# HM_Nightfall-mini_v1.net
KiCad netlist of a schematic drawn in EAGLE
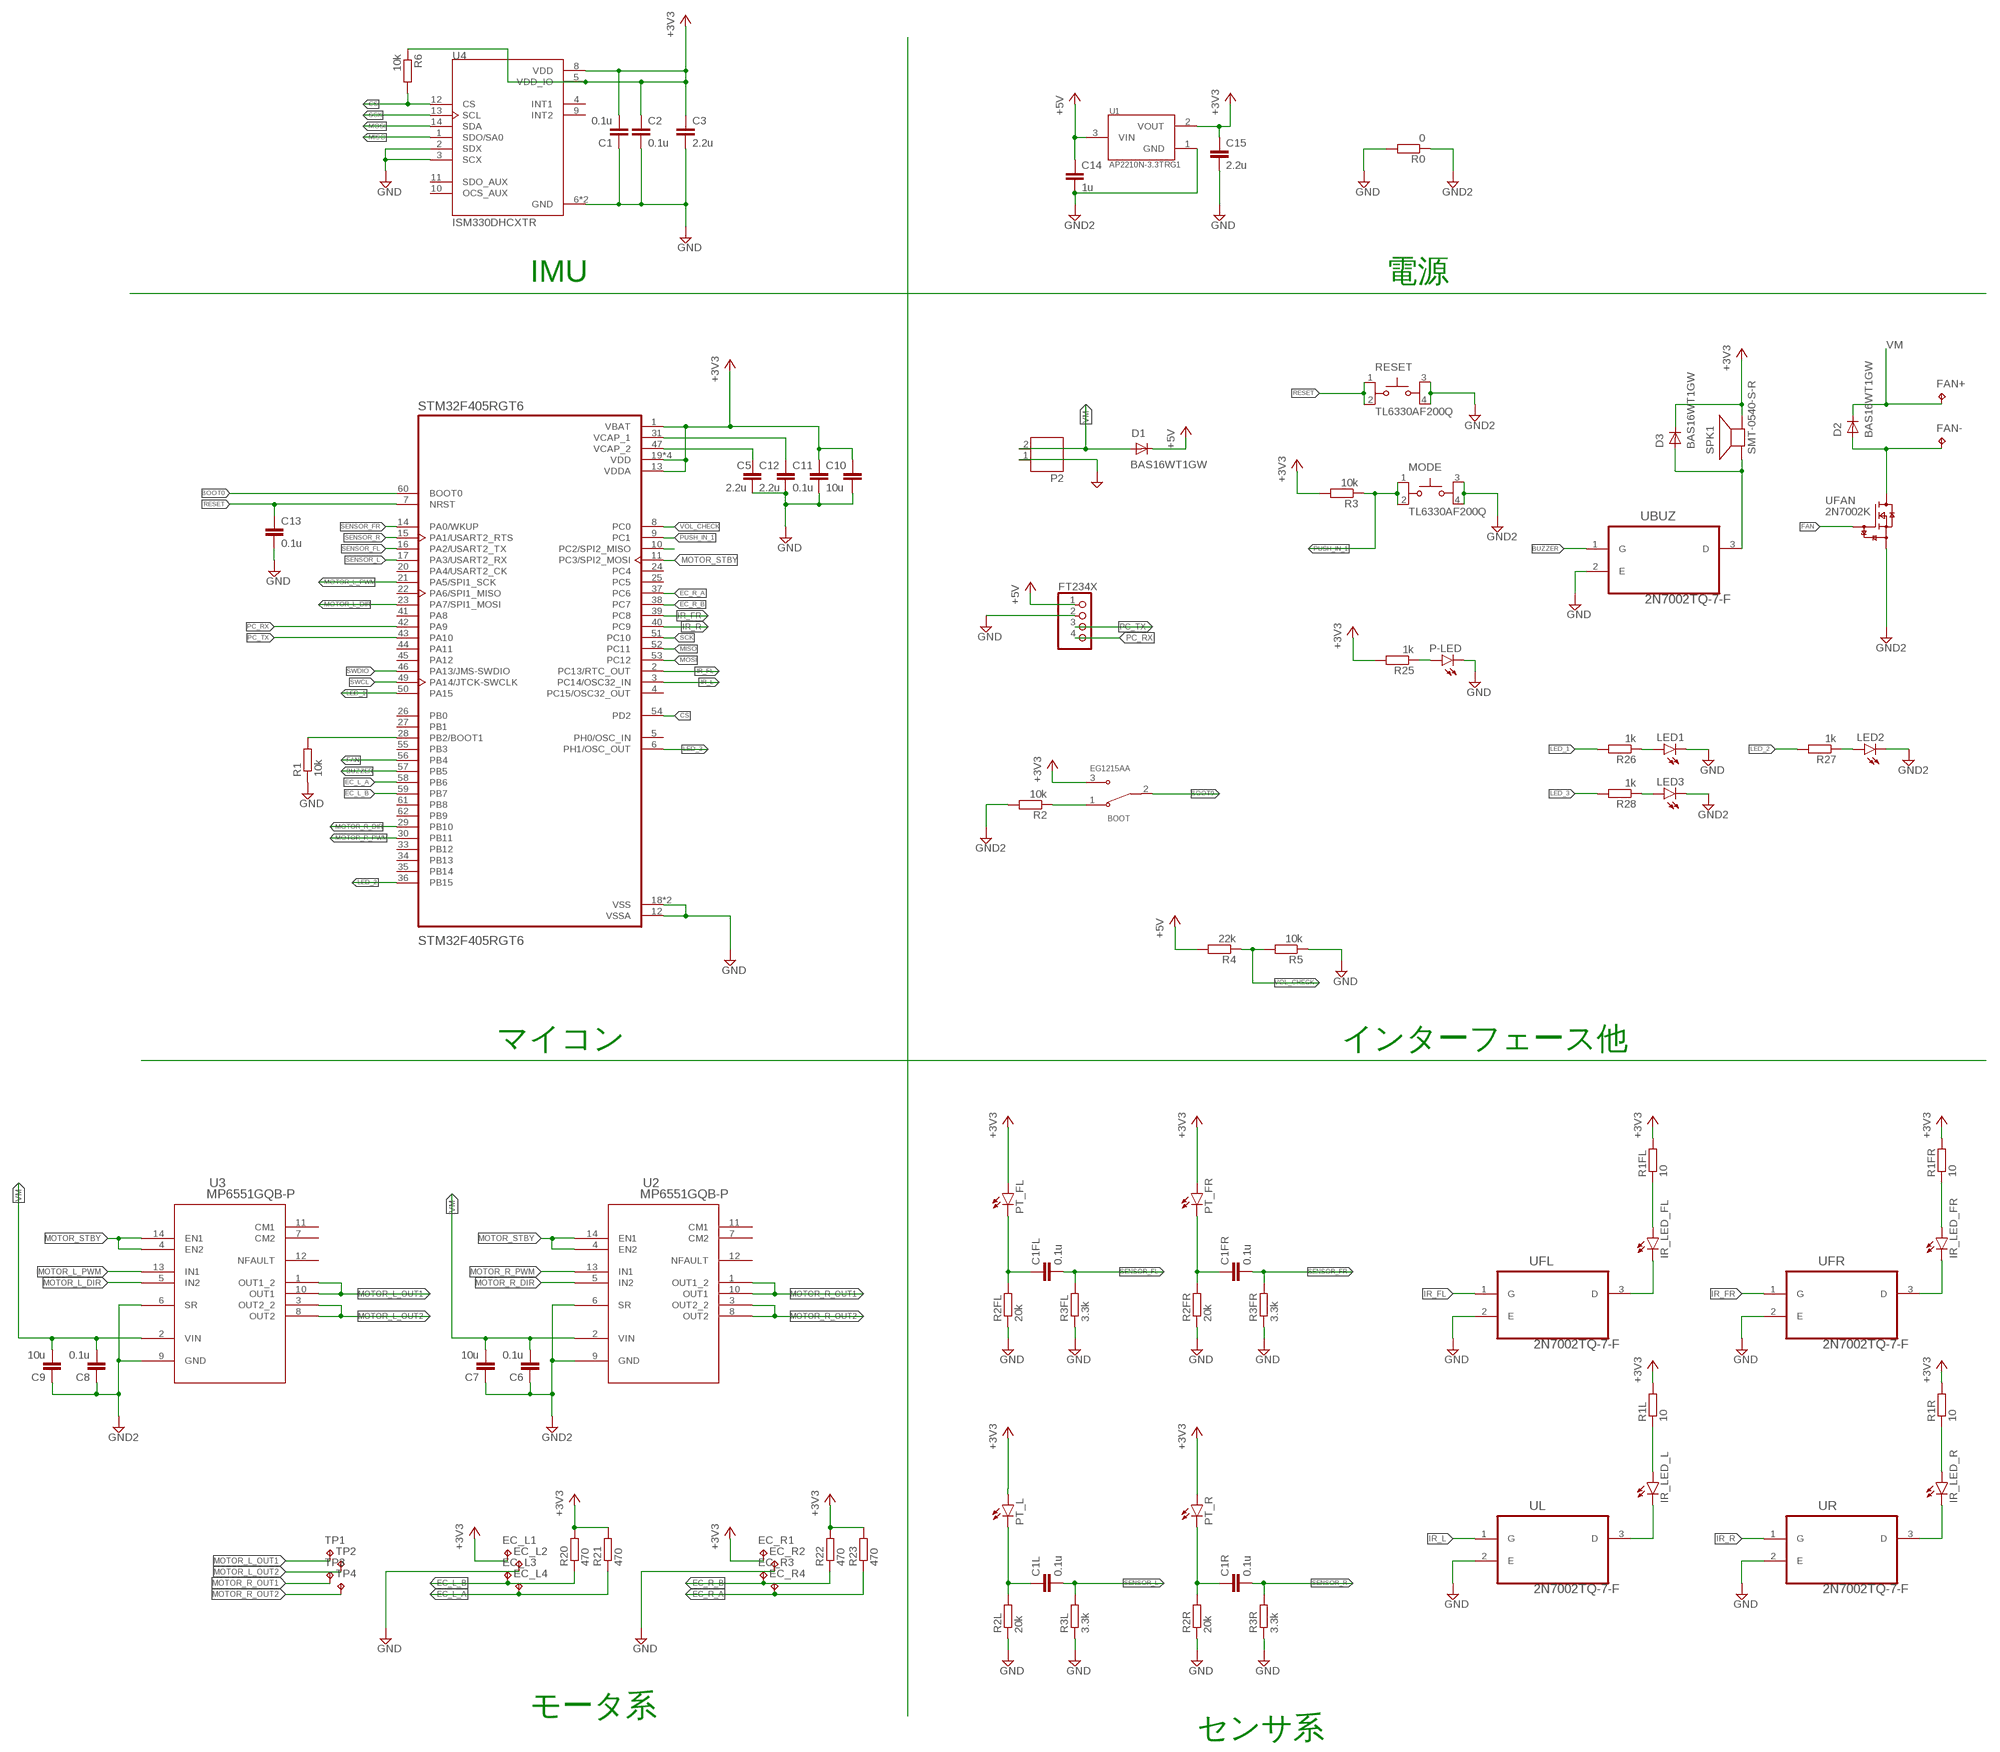
[diagram p0: schematic, sheet 1]

(export (version "E")
  (design (tool "Eeschema 10.0.6"))
  (components
    (comp (ref "BOOT")
      (value "EG1215AA")
      (footprint "eagle-import:SW_EG1215AA")
      (fields (field (name "MF") "E-Switch"))
      (libsource (lib "eagle-import") (part "EG1215AA"))
    )
    (comp (ref "C1")
      (value "0.1u")
      (footprint "eagle-import:C0402")
      (libsource (lib "eagle-import") (part "C-EUC0402"))
    )
    (comp (ref "C1FL")
      (value "0.1u")
      (footprint "eagle-import:C0402")
      (libsource (lib "eagle-import") (part "C-EUC0402"))
    )
    (comp (ref "C1FR")
      (value "0.1u")
      (footprint "eagle-import:C0402")
      (libsource (lib "eagle-import") (part "C-EUC0402"))
    )
    (comp (ref "C1L")
      (value "0.1u")
      (footprint "eagle-import:C0402")
      (libsource (lib "eagle-import") (part "C-EUC0402"))
    )
    (comp (ref "C1R")
      (value "0.1u")
      (footprint "eagle-import:C0402")
      (libsource (lib "eagle-import") (part "C-EUC0402"))
    )
    (comp (ref "C2")
      (value "0.1u")
      (footprint "eagle-import:C0402")
      (libsource (lib "eagle-import") (part "C-EUC0402"))
    )
    (comp (ref "C3")
      (value "2.2u")
      (footprint "eagle-import:C0402")
      (libsource (lib "eagle-import") (part "C-EUC0402"))
    )
    (comp (ref "C5")
      (value "2.2u")
      (footprint "eagle-import:C0402")
      (libsource (lib "eagle-import") (part "C-EUC0402"))
    )
    (comp (ref "C6")
      (value "0.1u")
      (footprint "eagle-import:C0402")
      (libsource (lib "eagle-import") (part "C-EUC0402"))
    )
    (comp (ref "C7")
      (value "10u")
      (footprint "eagle-import:C0402")
      (libsource (lib "eagle-import") (part "C-EUC0402"))
    )
    (comp (ref "C8")
      (value "0.1u")
      (footprint "eagle-import:C0402")
      (libsource (lib "eagle-import") (part "C-EUC0402"))
    )
    (comp (ref "C9")
      (value "10u")
      (footprint "eagle-import:C0402")
      (libsource (lib "eagle-import") (part "C-EUC0402"))
    )
    (comp (ref "C10")
      (value "10u")
      (footprint "eagle-import:C0402")
      (libsource (lib "eagle-import") (part "C-EUC0402"))
    )
    (comp (ref "C11")
      (value "0.1u")
      (footprint "eagle-import:C0402")
      (libsource (lib "eagle-import") (part "C-EUC0402"))
    )
    (comp (ref "C12")
      (value "2.2u")
      (footprint "eagle-import:C0402")
      (libsource (lib "eagle-import") (part "C-EUC0402"))
    )
    (comp (ref "C13")
      (value "0.1u")
      (footprint "eagle-import:C0402")
      (libsource (lib "eagle-import") (part "C-EUC0402"))
    )
    (comp (ref "C14")
      (value "1u")
      (footprint "eagle-import:C0402")
      (libsource (lib "eagle-import") (part "C-EUC0402"))
    )
    (comp (ref "C15")
      (value "2.2u")
      (footprint "eagle-import:C0402")
      (libsource (lib "eagle-import") (part "C-EUC0402"))
    )
    (comp (ref "D1")
      (value "BAS16WT1GW")
      (footprint "eagle-import:SOT323")
      (fields (field (name "MF") "ON Semiconductor") (field (name "MP") "BAS16WT1G"))
      (libsource (lib "eagle-import") (part "BAS16WT1GW"))
    )
    (comp (ref "D2")
      (value "BAS16WT1GW")
      (footprint "eagle-import:SOT323")
      (fields (field (name "MF") "ON Semiconductor") (field (name "MP") "BAS16WT1G"))
      (libsource (lib "eagle-import") (part "BAS16WT1GW"))
    )
    (comp (ref "D3")
      (value "BAS16WT1GW")
      (footprint "eagle-import:SOT323")
      (fields (field (name "MF") "ON Semiconductor") (field (name "MP") "BAS16WT1G"))
      (libsource (lib "eagle-import") (part "BAS16WT1GW"))
    )
    (comp (ref "EC_L1")
      (value "TPB1,27")
      (footprint "eagle-import:B1,27")
      (libsource (lib "eagle-import") (part "TPB1,27"))
    )
    (comp (ref "EC_L2")
      (value "TPB1,27")
      (footprint "eagle-import:B1,27")
      (libsource (lib "eagle-import") (part "TPB1,27"))
    )
    (comp (ref "EC_L3")
      (value "TPB1,27")
      (footprint "eagle-import:B1,27")
      (libsource (lib "eagle-import") (part "TPB1,27"))
    )
    (comp (ref "EC_L4")
      (value "TPB1,27")
      (footprint "eagle-import:B1,27")
      (libsource (lib "eagle-import") (part "TPB1,27"))
    )
    (comp (ref "EC_R1")
      (value "TPB1,27")
      (footprint "eagle-import:B1,27")
      (libsource (lib "eagle-import") (part "TPB1,27"))
    )
    (comp (ref "EC_R2")
      (value "TPB1,27")
      (footprint "eagle-import:B1,27")
      (libsource (lib "eagle-import") (part "TPB1,27"))
    )
    (comp (ref "EC_R3")
      (value "TPB1,27")
      (footprint "eagle-import:B1,27")
      (libsource (lib "eagle-import") (part "TPB1,27"))
    )
    (comp (ref "EC_R4")
      (value "TPB1,27")
      (footprint "eagle-import:B1,27")
      (libsource (lib "eagle-import") (part "TPB1,27"))
    )
    (comp (ref "FAN+")
      (value "TPB1,27")
      (footprint "eagle-import:B1,27")
      (libsource (lib "eagle-import") (part "TPB1,27"))
    )
    (comp (ref "FAN-")
      (value "TPB1,27")
      (footprint "eagle-import:B1,27")
      (libsource (lib "eagle-import") (part "TPB1,27"))
    )
    (comp (ref "FT234X")
      (value "PINHD-1X4")
      (footprint "eagle-import:1X04")
      (libsource (lib "eagle-import") (part "PINHD-1X4"))
    )
    (comp (ref "IR_LED_FL")
      (value "LED3MM")
      (footprint "eagle-import:LED3MM")
      (libsource (lib "eagle-import") (part "LED3MM"))
    )
    (comp (ref "IR_LED_FR")
      (value "LED3MM")
      (footprint "eagle-import:LED3MM")
      (libsource (lib "eagle-import") (part "LED3MM"))
    )
    (comp (ref "IR_LED_L")
      (value "LED3MM")
      (footprint "eagle-import:LED3MM")
      (libsource (lib "eagle-import") (part "LED3MM"))
    )
    (comp (ref "IR_LED_R")
      (value "LED3MM")
      (footprint "eagle-import:LED3MM")
      (libsource (lib "eagle-import") (part "LED3MM"))
    )
    (comp (ref "LED1")
      (value "LEDCHIPLED_0603")
      (footprint "eagle-import:CHIPLED_0603")
      (libsource (lib "eagle-import") (part "LEDCHIPLED_0603"))
    )
    (comp (ref "LED2")
      (value "LEDCHIPLED_0603")
      (footprint "eagle-import:CHIPLED_0603")
      (libsource (lib "eagle-import") (part "LEDCHIPLED_0603"))
    )
    (comp (ref "LED3")
      (value "LEDCHIPLED_0603")
      (footprint "eagle-import:CHIPLED_0603")
      (libsource (lib "eagle-import") (part "LEDCHIPLED_0603"))
    )
    (comp (ref "MODE")
      (value "TL6330AF200Q")
      (footprint "eagle-import:SW_TL6330AF200Q")
      (fields (field (name "MF") "E-Switch"))
      (libsource (lib "eagle-import") (part "TL6330AF200Q"))
    )
    (comp (ref "P-LED")
      (value "LEDCHIPLED_0603")
      (footprint "eagle-import:CHIPLED_0603")
      (libsource (lib "eagle-import") (part "LEDCHIPLED_0603"))
    )
    (comp (ref "P2")
      (value "JST-PH2")
      (footprint "eagle-import:JST-PH2")
      (libsource (lib "eagle-import") (part "JST-PH2"))
    )
    (comp (ref "PT_FL")
      (value "LED3MM")
      (footprint "eagle-import:LED3MM")
      (libsource (lib "eagle-import") (part "LED3MM"))
    )
    (comp (ref "PT_FR")
      (value "LED3MM")
      (footprint "eagle-import:LED3MM")
      (libsource (lib "eagle-import") (part "LED3MM"))
    )
    (comp (ref "PT_L")
      (value "LED3MM")
      (footprint "eagle-import:LED3MM")
      (libsource (lib "eagle-import") (part "LED3MM"))
    )
    (comp (ref "PT_R")
      (value "LED3MM")
      (footprint "eagle-import:LED3MM")
      (libsource (lib "eagle-import") (part "LED3MM"))
    )
    (comp (ref "R0")
      (value "0")
      (footprint "eagle-import:R0402")
      (libsource (lib "eagle-import") (part "R-EU_R0402"))
    )
    (comp (ref "R1")
      (value "10k")
      (footprint "eagle-import:R0402")
      (libsource (lib "eagle-import") (part "R-EU_R0402"))
    )
    (comp (ref "R1FL")
      (value "10")
      (footprint "eagle-import:R0402")
      (libsource (lib "eagle-import") (part "R-EU_R0402"))
    )
    (comp (ref "R1FR")
      (value "10")
      (footprint "eagle-import:R0402")
      (libsource (lib "eagle-import") (part "R-EU_R0402"))
    )
    (comp (ref "R1L")
      (value "10")
      (footprint "eagle-import:R0402")
      (libsource (lib "eagle-import") (part "R-EU_R0402"))
    )
    (comp (ref "R1R")
      (value "10")
      (footprint "eagle-import:R0402")
      (libsource (lib "eagle-import") (part "R-EU_R0402"))
    )
    (comp (ref "R2")
      (value "10k")
      (footprint "eagle-import:R0402")
      (libsource (lib "eagle-import") (part "R-EU_R0402"))
    )
    (comp (ref "R2FL")
      (value "20k")
      (footprint "eagle-import:R0402")
      (libsource (lib "eagle-import") (part "R-EU_R0402"))
    )
    (comp (ref "R2FR")
      (value "20k")
      (footprint "eagle-import:R0402")
      (libsource (lib "eagle-import") (part "R-EU_R0402"))
    )
    (comp (ref "R2L")
      (value "20k")
      (footprint "eagle-import:R0402")
      (libsource (lib "eagle-import") (part "R-EU_R0402"))
    )
    (comp (ref "R2R")
      (value "20k")
      (footprint "eagle-import:R0402")
      (libsource (lib "eagle-import") (part "R-EU_R0402"))
    )
    (comp (ref "R3")
      (value "10k")
      (footprint "eagle-import:R0402")
      (libsource (lib "eagle-import") (part "R-EU_R0402"))
    )
    (comp (ref "R3FL")
      (value "3.3k")
      (footprint "eagle-import:R0402")
      (libsource (lib "eagle-import") (part "R-EU_R0402"))
    )
    (comp (ref "R3FR")
      (value "3.3k")
      (footprint "eagle-import:R0402")
      (libsource (lib "eagle-import") (part "R-EU_R0402"))
    )
    (comp (ref "R3L")
      (value "3.3k")
      (footprint "eagle-import:R0402")
      (libsource (lib "eagle-import") (part "R-EU_R0402"))
    )
    (comp (ref "R3R")
      (value "3.3k")
      (footprint "eagle-import:R0402")
      (libsource (lib "eagle-import") (part "R-EU_R0402"))
    )
    (comp (ref "R4")
      (value "22k")
      (footprint "eagle-import:R0402")
      (libsource (lib "eagle-import") (part "R-EU_R0402"))
    )
    (comp (ref "R5")
      (value "10k")
      (footprint "eagle-import:R0402")
      (libsource (lib "eagle-import") (part "R-EU_R0402"))
    )
    (comp (ref "R6")
      (value "10k")
      (footprint "eagle-import:R0402")
      (libsource (lib "eagle-import") (part "R-EU_R0402"))
    )
    (comp (ref "R20")
      (value "470")
      (footprint "eagle-import:R0402")
      (libsource (lib "eagle-import") (part "R-EU_R0402"))
    )
    (comp (ref "R21")
      (value "470")
      (footprint "eagle-import:R0402")
      (libsource (lib "eagle-import") (part "R-EU_R0402"))
    )
    (comp (ref "R22")
      (value "470")
      (footprint "eagle-import:R0402")
      (libsource (lib "eagle-import") (part "R-EU_R0402"))
    )
    (comp (ref "R23")
      (value "470")
      (footprint "eagle-import:R0402")
      (libsource (lib "eagle-import") (part "R-EU_R0402"))
    )
    (comp (ref "R25")
      (value "1k")
      (footprint "eagle-import:R0402")
      (libsource (lib "eagle-import") (part "R-EU_R0402"))
    )
    (comp (ref "R26")
      (value "1k")
      (footprint "eagle-import:R0402")
      (libsource (lib "eagle-import") (part "R-EU_R0402"))
    )
    (comp (ref "R27")
      (value "1k")
      (footprint "eagle-import:R0402")
      (libsource (lib "eagle-import") (part "R-EU_R0402"))
    )
    (comp (ref "R28")
      (value "1k")
      (footprint "eagle-import:R0402")
      (libsource (lib "eagle-import") (part "R-EU_R0402"))
    )
    (comp (ref "RESET")
      (value "TL6330AF200Q")
      (footprint "eagle-import:SW_TL6330AF200Q")
      (fields (field (name "MF") "E-Switch"))
      (libsource (lib "eagle-import") (part "TL6330AF200Q"))
    )
    (comp (ref "SPK1")
      (value "SMT-0540-S-R")
      (footprint "eagle-import:SMT-0540-S-R")
      (fields (field (name "DIGI-KEY_PART_NUMBER") "668-1060-1-ND") (field (name "MF") "PUI"))
      (libsource (lib "eagle-import") (part "SMT-0540-S-R"))
    )
    (comp (ref "STM32F405RGT6")
      (value "STM32F405RGT6")
      (footprint "eagle-import:QFP50P1200X1200X160-64N")
      (fields (field (name "MF") "STMicroelectronics"))
      (libsource (lib "eagle-import") (part "STM32F405RGT6"))
    )
    (comp (ref "TP1")
      (value "TPB1,27")
      (footprint "eagle-import:B1,27")
      (libsource (lib "eagle-import") (part "TPB1,27"))
    )
    (comp (ref "TP2")
      (value "TPB1,27")
      (footprint "eagle-import:B1,27")
      (libsource (lib "eagle-import") (part "TPB1,27"))
    )
    (comp (ref "TP3")
      (value "TPB1,27")
      (footprint "eagle-import:B1,27")
      (libsource (lib "eagle-import") (part "TPB1,27"))
    )
    (comp (ref "TP4")
      (value "TPB1,27")
      (footprint "eagle-import:B1,27")
      (libsource (lib "eagle-import") (part "TPB1,27"))
    )
    (comp (ref "U1")
      (value "AP2210N-3.3TRG1")
      (footprint "eagle-import:SOT95P280X145-3N")
      (fields (field (name "MF") "Diodes Inc."))
      (libsource (lib "eagle-import") (part "AP2210N-3.3TRG1"))
    )
    (comp (ref "U2")
      (value "MP6551GQB-P")
      (footprint "eagle-import:QFN-14_MP6551_MNP")
      (fields (field (name "COPYRIGHT") "Copyright (C) 2025 Ultra Librarian. All rights reserved."))
      (libsource (lib "eagle-import") (part "MP6551GQB-P"))
    )
    (comp (ref "U3")
      (value "MP6551GQB-P")
      (footprint "eagle-import:QFN-14_MP6551_MNP")
      (fields (field (name "COPYRIGHT") "Copyright (C) 2025 Ultra Librarian. All rights reserved."))
      (libsource (lib "eagle-import") (part "MP6551GQB-P"))
    )
    (comp (ref "U4")
      (value "ISM330DHCXTR")
      (footprint "eagle-import:PQFN50P250X300X86-14N")
      (fields (field (name "MF") "STMicroelectronics"))
      (libsource (lib "eagle-import") (part "ISM330DHCXTR"))
    )
    (comp (ref "UBUZ")
      (value "2N7002TQ-7-F")
      (footprint "eagle-import:SOT50P160X90-3N")
      (fields (field (name "MF") "Diodes Inc."))
      (libsource (lib "eagle-import") (part "2N7002TQ-7-F"))
    )
    (comp (ref "UFAN")
      (value "2N7002K")
      (footprint "eagle-import:SOT23")
      (libsource (lib "eagle-import") (part "2N7002K"))
    )
    (comp (ref "UFL")
      (value "2N7002TQ-7-F")
      (footprint "eagle-import:SOT50P160X90-3N")
      (fields (field (name "MF") "Diodes Inc."))
      (libsource (lib "eagle-import") (part "2N7002TQ-7-F"))
    )
    (comp (ref "UFR")
      (value "2N7002TQ-7-F")
      (footprint "eagle-import:SOT50P160X90-3N")
      (fields (field (name "MF") "Diodes Inc."))
      (libsource (lib "eagle-import") (part "2N7002TQ-7-F"))
    )
    (comp (ref "UL")
      (value "2N7002TQ-7-F")
      (footprint "eagle-import:SOT50P160X90-3N")
      (fields (field (name "MF") "Diodes Inc."))
      (libsource (lib "eagle-import") (part "2N7002TQ-7-F"))
    )
    (comp (ref "UR")
      (value "2N7002TQ-7-F")
      (footprint "eagle-import:SOT50P160X90-3N")
      (fields (field (name "MF") "Diodes Inc."))
      (libsource (lib "eagle-import") (part "2N7002TQ-7-F"))
    )
  )
  (nets
    (net (code "1") (name "+3V3") (class "Default")
      (node (ref "BOOT") (pin "3") (pinfunction "3_3") (pintype "passive"))
      (node (ref "C1") (pin "2") (pinfunction "2_2") (pintype "passive"))
      (node (ref "C10") (pin "1") (pinfunction "1_1") (pintype "passive"))
      (node (ref "C11") (pin "1") (pinfunction "1_1") (pintype "passive"))
      (node (ref "C15") (pin "1") (pinfunction "1_1") (pintype "passive"))
      (node (ref "C2") (pin "1") (pinfunction "1_1") (pintype "passive"))
      (node (ref "C3") (pin "1") (pinfunction "1_1") (pintype "passive"))
      (node (ref "D3") (pin "3") (pinfunction "K_3") (pintype "passive"))
      (node (ref "EC_L1") (pin "TP") (pinfunction "TP_TP") (pintype "input"))
      (node (ref "EC_R1") (pin "TP") (pinfunction "TP_TP") (pintype "input"))
      (node (ref "PT_FL") (pin "A") (pinfunction "A_A") (pintype "passive"))
      (node (ref "PT_FR") (pin "A") (pinfunction "A_A") (pintype "passive"))
      (node (ref "PT_L") (pin "A") (pinfunction "A_A") (pintype "passive"))
      (node (ref "PT_R") (pin "A") (pinfunction "A_A") (pintype "passive"))
      (node (ref "R1FL") (pin "2") (pinfunction "2_2") (pintype "passive"))
      (node (ref "R1FR") (pin "2") (pinfunction "2_2") (pintype "passive"))
      (node (ref "R1L") (pin "2") (pinfunction "2_2") (pintype "passive"))
      (node (ref "R1R") (pin "2") (pinfunction "2_2") (pintype "passive"))
      (node (ref "R20") (pin "2") (pinfunction "2_2") (pintype "passive"))
      (node (ref "R21") (pin "2") (pinfunction "2_2") (pintype "passive"))
      (node (ref "R22") (pin "2") (pinfunction "2_2") (pintype "passive"))
      (node (ref "R23") (pin "2") (pinfunction "2_2") (pintype "passive"))
      (node (ref "R25") (pin "2") (pinfunction "2_2") (pintype "passive"))
      (node (ref "R3") (pin "2") (pinfunction "2_2") (pintype "passive"))
      (node (ref "R6") (pin "1") (pinfunction "1_1") (pintype "passive"))
      (node (ref "SPK1") (pin "+") (pinfunction "-_+") (pintype "passive"))
      (node (ref "STM32F405RGT6") (pin "1") (pinfunction "VBAT_1") (pintype "power_in"))
      (node (ref "STM32F405RGT6") (pin "13") (pinfunction "VDDA_13") (pintype "power_in"))
      (node (ref "STM32F405RGT6") (pin "19") (pinfunction "VDD_19") (pintype "power_in"))
      (node (ref "STM32F405RGT6") (pin "32") (pinfunction "VDD_32") (pintype "power_in"))
      (node (ref "STM32F405RGT6") (pin "48") (pinfunction "VDD_48") (pintype "power_in"))
      (node (ref "STM32F405RGT6") (pin "64") (pinfunction "VDD_64") (pintype "power_in"))
      (node (ref "U1") (pin "2") (pinfunction "VOUT_2") (pintype "output"))
      (node (ref "U4") (pin "5") (pinfunction "VDD_IO_5") (pintype "power_in"))
      (node (ref "U4") (pin "8") (pinfunction "VDD_8") (pintype "power_in"))
    )
    (net (code "2") (name "+5V") (class "Default")
      (node (ref "C14") (pin "1") (pinfunction "1_1") (pintype "passive"))
      (node (ref "D1") (pin "3") (pinfunction "K_3") (pintype "passive"))
      (node (ref "FT234X") (pin "1") (pinfunction "1_1") (pintype "passive"))
      (node (ref "R4") (pin "2") (pinfunction "2_2") (pintype "passive"))
      (node (ref "U1") (pin "3") (pinfunction "VIN_3") (pintype "input"))
    )
    (net (code "3") (name "BOOT0") (class "Default")
      (node (ref "BOOT") (pin "2") (pinfunction "2_2") (pintype "passive"))
      (node (ref "STM32F405RGT6") (pin "60") (pinfunction "BOOT0_60") (pintype "bidirectional"))
    )
    (net (code "4") (name "BUZZER") (class "Default")
      (node (ref "STM32F405RGT6") (pin "57") (pinfunction "PB5_57") (pintype "bidirectional"))
      (node (ref "UBUZ") (pin "1") (pinfunction "G_1") (pintype "passive"))
    )
    (net (code "5") (name "CS") (class "Default")
      (node (ref "R6") (pin "2") (pinfunction "2_2") (pintype "passive"))
      (node (ref "STM32F405RGT6") (pin "54") (pinfunction "PD2_54") (pintype "bidirectional"))
      (node (ref "U4") (pin "12") (pinfunction "CS_12") (pintype "input"))
    )
    (net (code "6") (name "EC_L_A") (class "Default")
      (node (ref "EC_L4") (pin "TP") (pinfunction "TP_TP") (pintype "input"))
      (node (ref "R21") (pin "1") (pinfunction "1_1") (pintype "passive"))
      (node (ref "STM32F405RGT6") (pin "58") (pinfunction "PB6_58") (pintype "bidirectional"))
    )
    (net (code "7") (name "EC_L_B") (class "Default")
      (node (ref "EC_L3") (pin "TP") (pinfunction "TP_TP") (pintype "input"))
      (node (ref "R20") (pin "1") (pinfunction "1_1") (pintype "passive"))
      (node (ref "STM32F405RGT6") (pin "59") (pinfunction "PB7_59") (pintype "bidirectional"))
    )
    (net (code "8") (name "EC_R_A") (class "Default")
      (node (ref "EC_R4") (pin "TP") (pinfunction "TP_TP") (pintype "input"))
      (node (ref "R23") (pin "1") (pinfunction "1_1") (pintype "passive"))
      (node (ref "STM32F405RGT6") (pin "37") (pinfunction "PC6_37") (pintype "bidirectional"))
    )
    (net (code "9") (name "EC_R_B") (class "Default")
      (node (ref "EC_R3") (pin "TP") (pinfunction "TP_TP") (pintype "input"))
      (node (ref "R22") (pin "1") (pinfunction "1_1") (pintype "passive"))
      (node (ref "STM32F405RGT6") (pin "38") (pinfunction "PC7_38") (pintype "bidirectional"))
    )
    (net (code "10") (name "FAN") (class "Default")
      (node (ref "STM32F405RGT6") (pin "56") (pinfunction "PB4_56") (pintype "bidirectional"))
      (node (ref "UFAN") (pin "1") (pinfunction "G_1") (pintype "passive"))
    )
    (net (code "11") (name "GND") (class "Default")
      (node (ref "C1") (pin "1") (pinfunction "1_1") (pintype "passive"))
      (node (ref "C10") (pin "2") (pinfunction "2_2") (pintype "passive"))
      (node (ref "C11") (pin "2") (pinfunction "2_2") (pintype "passive"))
      (node (ref "C12") (pin "2") (pinfunction "2_2") (pintype "passive"))
      (node (ref "C13") (pin "2") (pinfunction "2_2") (pintype "passive"))
      (node (ref "C15") (pin "2") (pinfunction "2_2") (pintype "passive"))
      (node (ref "C2") (pin "2") (pinfunction "2_2") (pintype "passive"))
      (node (ref "C3") (pin "2") (pinfunction "2_2") (pintype "passive"))
      (node (ref "C5") (pin "2") (pinfunction "2_2") (pintype "passive"))
      (node (ref "EC_L2") (pin "TP") (pinfunction "TP_TP") (pintype "input"))
      (node (ref "EC_R2") (pin "TP") (pinfunction "TP_TP") (pintype "input"))
      (node (ref "FT234X") (pin "2") (pinfunction "2_2") (pintype "passive"))
      (node (ref "LED1") (pin "C") (pinfunction "C_C") (pintype "passive"))
      (node (ref "P-LED") (pin "C") (pinfunction "C_C") (pintype "passive"))
      (node (ref "R0") (pin "2") (pinfunction "2_2") (pintype "passive"))
      (node (ref "R1") (pin "1") (pinfunction "1_1") (pintype "passive"))
      (node (ref "R2FL") (pin "1") (pinfunction "1_1") (pintype "passive"))
      (node (ref "R2FR") (pin "1") (pinfunction "1_1") (pintype "passive"))
      (node (ref "R2L") (pin "1") (pinfunction "1_1") (pintype "passive"))
      (node (ref "R2R") (pin "1") (pinfunction "1_1") (pintype "passive"))
      (node (ref "R3FL") (pin "1") (pinfunction "1_1") (pintype "passive"))
      (node (ref "R3FR") (pin "1") (pinfunction "1_1") (pintype "passive"))
      (node (ref "R3L") (pin "1") (pinfunction "1_1") (pintype "passive"))
      (node (ref "R3R") (pin "1") (pinfunction "1_1") (pintype "passive"))
      (node (ref "R5") (pin "1") (pinfunction "1_1") (pintype "passive"))
      (node (ref "STM32F405RGT6") (pin "12") (pinfunction "VSSA_12") (pintype "power_in"))
      (node (ref "STM32F405RGT6") (pin "18") (pinfunction "VSS_18") (pintype "power_in"))
      (node (ref "STM32F405RGT6") (pin "63") (pinfunction "VSS_63") (pintype "power_in"))
      (node (ref "U4") (pin "2") (pinfunction "SDX_2") (pintype "bidirectional"))
      (node (ref "U4") (pin "3") (pinfunction "SCX_3") (pintype "bidirectional"))
      (node (ref "U4") (pin "6") (pinfunction "GND_6") (pintype "power_in"))
      (node (ref "U4") (pin "7") (pinfunction "GND_7") (pintype "power_in"))
      (node (ref "UBUZ") (pin "2") (pinfunction "E_2") (pintype "passive"))
      (node (ref "UFL") (pin "2") (pinfunction "E_2") (pintype "passive"))
      (node (ref "UFR") (pin "2") (pinfunction "E_2") (pintype "passive"))
      (node (ref "UL") (pin "2") (pinfunction "E_2") (pintype "passive"))
      (node (ref "UR") (pin "2") (pinfunction "E_2") (pintype "passive"))
    )
    (net (code "12") (name "GND2") (class "Default")
      (node (ref "C14") (pin "2") (pinfunction "2_2") (pintype "passive"))
      (node (ref "C6") (pin "1") (pinfunction "1_1") (pintype "passive"))
      (node (ref "C7") (pin "1") (pinfunction "1_1") (pintype "passive"))
      (node (ref "C8") (pin "1") (pinfunction "1_1") (pintype "passive"))
      (node (ref "C9") (pin "1") (pinfunction "1_1") (pintype "passive"))
      (node (ref "LED2") (pin "C") (pinfunction "C_C") (pintype "passive"))
      (node (ref "LED3") (pin "C") (pinfunction "C_C") (pintype "passive"))
      (node (ref "MODE") (pin "3") (pinfunction "3_3") (pintype "passive"))
      (node (ref "MODE") (pin "4") (pinfunction "4_4") (pintype "passive"))
      (node (ref "P2") (pin "1") (pinfunction "1_1") (pintype "passive"))
      (node (ref "R0") (pin "1") (pinfunction "1_1") (pintype "passive"))
      (node (ref "R2") (pin "2") (pinfunction "2_2") (pintype "passive"))
      (node (ref "RESET") (pin "3") (pinfunction "3_3") (pintype "passive"))
      (node (ref "RESET") (pin "4") (pinfunction "4_4") (pintype "passive"))
      (node (ref "U1") (pin "1") (pinfunction "GND_1") (pintype "power_in"))
      (node (ref "U2") (pin "6") (pinfunction "SR_6") (pintype "passive"))
      (node (ref "U2") (pin "9") (pinfunction "GND_9") (pintype "power_in"))
      (node (ref "U3") (pin "6") (pinfunction "SR_6") (pintype "passive"))
      (node (ref "U3") (pin "9") (pinfunction "GND_9") (pintype "power_in"))
      (node (ref "UFAN") (pin "2") (pinfunction "S_2") (pintype "passive"))
    )
    (net (code "13") (name "IR_FL") (class "Default")
      (node (ref "STM32F405RGT6") (pin "2") (pinfunction "PC13/RTC_OUT_2") (pintype "bidirectional"))
      (node (ref "UFL") (pin "1") (pinfunction "G_1") (pintype "passive"))
    )
    (net (code "14") (name "IR_FR") (class "Default")
      (node (ref "STM32F405RGT6") (pin "39") (pinfunction "PC8_39") (pintype "bidirectional"))
      (node (ref "UFR") (pin "1") (pinfunction "G_1") (pintype "passive"))
    )
    (net (code "15") (name "IR_L") (class "Default")
      (node (ref "STM32F405RGT6") (pin "3") (pinfunction "PC14/OSC32_IN_3") (pintype "bidirectional"))
      (node (ref "UL") (pin "1") (pinfunction "G_1") (pintype "passive"))
    )
    (net (code "16") (name "IR_R") (class "Default")
      (node (ref "STM32F405RGT6") (pin "40") (pinfunction "PC9_40") (pintype "bidirectional"))
      (node (ref "UR") (pin "1") (pinfunction "G_1") (pintype "passive"))
    )
    (net (code "17") (name "LED_1") (class "Default")
      (node (ref "R26") (pin "2") (pinfunction "2_2") (pintype "passive"))
      (node (ref "STM32F405RGT6") (pin "50") (pinfunction "PA15_50") (pintype "bidirectional"))
    )
    (net (code "18") (name "LED_2") (class "Default")
      (node (ref "R27") (pin "2") (pinfunction "2_2") (pintype "passive"))
      (node (ref "STM32F405RGT6") (pin "36") (pinfunction "PB15_36") (pintype "bidirectional"))
    )
    (net (code "19") (name "LED_3") (class "Default")
      (node (ref "R28") (pin "2") (pinfunction "2_2") (pintype "passive"))
      (node (ref "STM32F405RGT6") (pin "6") (pinfunction "PH1/OSC_OUT_6") (pintype "bidirectional"))
    )
    (net (code "20") (name "MISO") (class "Default")
      (node (ref "STM32F405RGT6") (pin "52") (pinfunction "PC11_52") (pintype "bidirectional"))
      (node (ref "U4") (pin "1") (pinfunction "SDO/SA0_1") (pintype "bidirectional"))
    )
    (net (code "21") (name "MOSI") (class "Default")
      (node (ref "STM32F405RGT6") (pin "53") (pinfunction "PC12_53") (pintype "bidirectional"))
      (node (ref "U4") (pin "14") (pinfunction "SDA_14") (pintype "bidirectional"))
    )
    (net (code "22") (name "MOTOR_L_DIR") (class "Default")
      (node (ref "STM32F405RGT6") (pin "23") (pinfunction "PA7/SPI1_MOSI_23") (pintype "bidirectional"))
      (node (ref "U3") (pin "5") (pinfunction "IN2_5") (pintype "input"))
    )
    (net (code "23") (name "MOTOR_L_OUT1") (class "Default")
      (node (ref "TP1") (pin "TP") (pinfunction "TP_TP") (pintype "input"))
      (node (ref "U3") (pin "1") (pinfunction "OUT1_2_1") (pintype "output"))
      (node (ref "U3") (pin "10") (pinfunction "OUT1_10") (pintype "output"))
    )
    (net (code "24") (name "MOTOR_L_OUT2") (class "Default")
      (node (ref "TP2") (pin "TP") (pinfunction "TP_TP") (pintype "input"))
      (node (ref "U3") (pin "3") (pinfunction "OUT2_2_3") (pintype "output"))
      (node (ref "U3") (pin "8") (pinfunction "OUT2_8") (pintype "output"))
    )
    (net (code "25") (name "MOTOR_L_PWM") (class "Default")
      (node (ref "STM32F405RGT6") (pin "21") (pinfunction "PA5/SPI1_SCK_21") (pintype "bidirectional"))
      (node (ref "U3") (pin "13") (pinfunction "IN1_13") (pintype "input"))
    )
    (net (code "26") (name "MOTOR_R_DIR") (class "Default")
      (node (ref "STM32F405RGT6") (pin "29") (pinfunction "PB10_29") (pintype "bidirectional"))
      (node (ref "U2") (pin "5") (pinfunction "IN2_5") (pintype "input"))
    )
    (net (code "27") (name "MOTOR_R_OUT1") (class "Default")
      (node (ref "TP3") (pin "TP") (pinfunction "TP_TP") (pintype "input"))
      (node (ref "U2") (pin "1") (pinfunction "OUT1_2_1") (pintype "output"))
      (node (ref "U2") (pin "10") (pinfunction "OUT1_10") (pintype "output"))
    )
    (net (code "28") (name "MOTOR_R_OUT2") (class "Default")
      (node (ref "TP4") (pin "TP") (pinfunction "TP_TP") (pintype "input"))
      (node (ref "U2") (pin "3") (pinfunction "OUT2_2_3") (pintype "output"))
      (node (ref "U2") (pin "8") (pinfunction "OUT2_8") (pintype "output"))
    )
    (net (code "29") (name "MOTOR_R_PWM") (class "Default")
      (node (ref "STM32F405RGT6") (pin "30") (pinfunction "PB11_30") (pintype "bidirectional"))
      (node (ref "U2") (pin "13") (pinfunction "IN1_13") (pintype "input"))
    )
    (net (code "30") (name "MOTOR_STBY") (class "Default")
      (node (ref "STM32F405RGT6") (pin "11") (pinfunction "PC3/SPI2_MOSI_11") (pintype "bidirectional"))
      (node (ref "U2") (pin "14") (pinfunction "EN1_14") (pintype "input"))
      (node (ref "U2") (pin "4") (pinfunction "EN2_4") (pintype "input"))
      (node (ref "U3") (pin "14") (pinfunction "EN1_14") (pintype "input"))
      (node (ref "U3") (pin "4") (pinfunction "EN2_4") (pintype "input"))
    )
    (net (code "31") (name "Net-(BOOT-Pad1)") (class "Default")
      (node (ref "BOOT") (pin "1") (pinfunction "1_1") (pintype "passive"))
      (node (ref "R2") (pin "1") (pinfunction "1_1") (pintype "passive"))
    )
    (net (code "32") (name "Net-(D2-A)") (class "Default")
      (node (ref "D2") (pin "1") (pinfunction "A_1") (pintype "passive"))
      (node (ref "FAN-") (pin "TP") (pinfunction "TP_TP") (pintype "input"))
      (node (ref "UFAN") (pin "3") (pinfunction "D_3") (pintype "passive"))
    )
    (net (code "33") (name "Net-(D3-A)") (class "Default")
      (node (ref "D3") (pin "1") (pinfunction "A_1") (pintype "passive"))
      (node (ref "SPK1") (pin "-") (pinfunction "+_-") (pintype "passive"))
      (node (ref "UBUZ") (pin "3") (pinfunction "D_3") (pintype "passive"))
    )
    (net (code "34") (name "Net-(IR_LED_FL-C)") (class "Default")
      (node (ref "IR_LED_FL") (pin "K") (pinfunction "C_K") (pintype "passive"))
      (node (ref "UFL") (pin "3") (pinfunction "D_3") (pintype "passive"))
    )
    (net (code "35") (name "Net-(IR_LED_FL-PadA)") (class "Default")
      (node (ref "IR_LED_FL") (pin "A") (pinfunction "A_A") (pintype "passive"))
      (node (ref "R1FL") (pin "1") (pinfunction "1_1") (pintype "passive"))
    )
    (net (code "36") (name "Net-(IR_LED_FR-C)") (class "Default")
      (node (ref "IR_LED_FR") (pin "K") (pinfunction "C_K") (pintype "passive"))
      (node (ref "UFR") (pin "3") (pinfunction "D_3") (pintype "passive"))
    )
    (net (code "37") (name "Net-(IR_LED_FR-PadA)") (class "Default")
      (node (ref "IR_LED_FR") (pin "A") (pinfunction "A_A") (pintype "passive"))
      (node (ref "R1FR") (pin "1") (pinfunction "1_1") (pintype "passive"))
    )
    (net (code "38") (name "Net-(IR_LED_L-C)") (class "Default")
      (node (ref "IR_LED_L") (pin "K") (pinfunction "C_K") (pintype "passive"))
      (node (ref "UL") (pin "3") (pinfunction "D_3") (pintype "passive"))
    )
    (net (code "39") (name "Net-(IR_LED_L-PadA)") (class "Default")
      (node (ref "IR_LED_L") (pin "A") (pinfunction "A_A") (pintype "passive"))
      (node (ref "R1L") (pin "1") (pinfunction "1_1") (pintype "passive"))
    )
    (net (code "40") (name "Net-(IR_LED_R-C)") (class "Default")
      (node (ref "IR_LED_R") (pin "K") (pinfunction "C_K") (pintype "passive"))
      (node (ref "UR") (pin "3") (pinfunction "D_3") (pintype "passive"))
    )
    (net (code "41") (name "Net-(IR_LED_R-PadA)") (class "Default")
      (node (ref "IR_LED_R") (pin "A") (pinfunction "A_A") (pintype "passive"))
      (node (ref "R1R") (pin "1") (pinfunction "1_1") (pintype "passive"))
    )
    (net (code "42") (name "Net-(LED1-PadA)") (class "Default")
      (node (ref "LED1") (pin "A") (pinfunction "A_A") (pintype "passive"))
      (node (ref "R26") (pin "1") (pinfunction "1_1") (pintype "passive"))
    )
    (net (code "43") (name "Net-(LED2-PadA)") (class "Default")
      (node (ref "LED2") (pin "A") (pinfunction "A_A") (pintype "passive"))
      (node (ref "R27") (pin "1") (pinfunction "1_1") (pintype "passive"))
    )
    (net (code "44") (name "Net-(LED3-PadA)") (class "Default")
      (node (ref "LED3") (pin "A") (pinfunction "A_A") (pintype "passive"))
      (node (ref "R28") (pin "1") (pinfunction "1_1") (pintype "passive"))
    )
    (net (code "45") (name "Net-(P-LED-PadA)") (class "Default")
      (node (ref "P-LED") (pin "A") (pinfunction "A_A") (pintype "passive"))
      (node (ref "R25") (pin "1") (pinfunction "1_1") (pintype "passive"))
    )
    (net (code "46") (name "Net-(PT_FL-C)") (class "Default")
      (node (ref "C1FL") (pin "1") (pinfunction "1_1") (pintype "passive"))
      (node (ref "PT_FL") (pin "K") (pinfunction "C_K") (pintype "passive"))
      (node (ref "R2FL") (pin "2") (pinfunction "2_2") (pintype "passive"))
    )
    (net (code "47") (name "Net-(PT_FR-C)") (class "Default")
      (node (ref "C1FR") (pin "1") (pinfunction "1_1") (pintype "passive"))
      (node (ref "PT_FR") (pin "K") (pinfunction "C_K") (pintype "passive"))
      (node (ref "R2FR") (pin "2") (pinfunction "2_2") (pintype "passive"))
    )
    (net (code "48") (name "Net-(PT_L-C)") (class "Default")
      (node (ref "C1L") (pin "1") (pinfunction "1_1") (pintype "passive"))
      (node (ref "PT_L") (pin "K") (pinfunction "C_K") (pintype "passive"))
      (node (ref "R2L") (pin "2") (pinfunction "2_2") (pintype "passive"))
    )
    (net (code "49") (name "Net-(PT_R-C)") (class "Default")
      (node (ref "C1R") (pin "1") (pinfunction "1_1") (pintype "passive"))
      (node (ref "PT_R") (pin "K") (pinfunction "C_K") (pintype "passive"))
      (node (ref "R2R") (pin "2") (pinfunction "2_2") (pintype "passive"))
    )
    (net (code "50") (name "Net-(STM32F405RGT6-PB2{slash}BOOT1)") (class "Default")
      (node (ref "R1") (pin "2") (pinfunction "2_2") (pintype "passive"))
      (node (ref "STM32F405RGT6") (pin "28") (pinfunction "PB2/BOOT1_28") (pintype "bidirectional"))
    )
    (net (code "51") (name "Net-(STM32F405RGT6-VCAP_1)") (class "Default")
      (node (ref "C12") (pin "1") (pinfunction "1_1") (pintype "passive"))
      (node (ref "STM32F405RGT6") (pin "31") (pinfunction "VCAP_1_31") (pintype "power_in"))
    )
    (net (code "52") (name "Net-(STM32F405RGT6-VCAP_2)") (class "Default")
      (node (ref "C5") (pin "1") (pinfunction "1_1") (pintype "passive"))
      (node (ref "STM32F405RGT6") (pin "47") (pinfunction "VCAP_2_47") (pintype "power_in"))
    )
    (net (code "53") (name "PC_RX") (class "Default")
      (node (ref "FT234X") (pin "4") (pinfunction "4_4") (pintype "passive"))
      (node (ref "STM32F405RGT6") (pin "42") (pinfunction "PA9_42") (pintype "bidirectional"))
    )
    (net (code "54") (name "PC_TX") (class "Default")
      (node (ref "FT234X") (pin "3") (pinfunction "3_3") (pintype "passive"))
      (node (ref "STM32F405RGT6") (pin "43") (pinfunction "PA10_43") (pintype "bidirectional"))
    )
    (net (code "55") (name "PUSH_IN_1") (class "Default")
      (node (ref "MODE") (pin "1") (pinfunction "1_1") (pintype "passive"))
      (node (ref "MODE") (pin "2") (pinfunction "2_2") (pintype "passive"))
      (node (ref "R3") (pin "1") (pinfunction "1_1") (pintype "passive"))
      (node (ref "STM32F405RGT6") (pin "9") (pinfunction "PC1_9") (pintype "bidirectional"))
    )
    (net (code "56") (name "RESET") (class "Default")
      (node (ref "C13") (pin "1") (pinfunction "1_1") (pintype "passive"))
      (node (ref "RESET") (pin "1") (pinfunction "1_1") (pintype "passive"))
      (node (ref "RESET") (pin "2") (pinfunction "2_2") (pintype "passive"))
      (node (ref "STM32F405RGT6") (pin "7") (pinfunction "NRST_7") (pintype "bidirectional"))
    )
    (net (code "57") (name "SCK") (class "Default")
      (node (ref "STM32F405RGT6") (pin "51") (pinfunction "PC10_51") (pintype "bidirectional"))
      (node (ref "U4") (pin "13") (pinfunction "SCL_13") (pintype "input"))
    )
    (net (code "58") (name "SENSOR_FL") (class "Default")
      (node (ref "C1FL") (pin "2") (pinfunction "2_2") (pintype "passive"))
      (node (ref "R3FL") (pin "2") (pinfunction "2_2") (pintype "passive"))
      (node (ref "STM32F405RGT6") (pin "16") (pinfunction "PA2/USART2_TX_16") (pintype "bidirectional"))
    )
    (net (code "59") (name "SENSOR_FR") (class "Default")
      (node (ref "C1FR") (pin "2") (pinfunction "2_2") (pintype "passive"))
      (node (ref "R3FR") (pin "2") (pinfunction "2_2") (pintype "passive"))
      (node (ref "STM32F405RGT6") (pin "14") (pinfunction "PA0/WKUP_14") (pintype "bidirectional"))
    )
    (net (code "60") (name "SENSOR_L") (class "Default")
      (node (ref "C1L") (pin "2") (pinfunction "2_2") (pintype "passive"))
      (node (ref "R3L") (pin "2") (pinfunction "2_2") (pintype "passive"))
      (node (ref "STM32F405RGT6") (pin "17") (pinfunction "PA3/USART2_RX_17") (pintype "bidirectional"))
    )
    (net (code "61") (name "SENSOR_R") (class "Default")
      (node (ref "C1R") (pin "2") (pinfunction "2_2") (pintype "passive"))
      (node (ref "R3R") (pin "2") (pinfunction "2_2") (pintype "passive"))
      (node (ref "STM32F405RGT6") (pin "15") (pinfunction "PA1/USART2_RTS_15") (pintype "bidirectional"))
    )
    (net (code "62") (name "SWCL") (class "Default")
      (node (ref "STM32F405RGT6") (pin "49") (pinfunction "PA14/JTCK-SWCLK_49") (pintype "bidirectional"))
    )
    (net (code "63") (name "SWDIO") (class "Default")
      (node (ref "STM32F405RGT6") (pin "46") (pinfunction "PA13/JMS-SWDIO_46") (pintype "bidirectional"))
    )
    (net (code "64") (name "VM") (class "Default")
      (node (ref "C6") (pin "2") (pinfunction "2_2") (pintype "passive"))
      (node (ref "C7") (pin "2") (pinfunction "2_2") (pintype "passive"))
      (node (ref "C8") (pin "2") (pinfunction "2_2") (pintype "passive"))
      (node (ref "C9") (pin "2") (pinfunction "2_2") (pintype "passive"))
      (node (ref "D1") (pin "1") (pinfunction "A_1") (pintype "passive"))
      (node (ref "D2") (pin "3") (pinfunction "K_3") (pintype "passive"))
      (node (ref "FAN+") (pin "TP") (pinfunction "TP_TP") (pintype "input"))
      (node (ref "P2") (pin "2") (pinfunction "2_2") (pintype "passive"))
      (node (ref "U2") (pin "2") (pinfunction "VIN_2") (pintype "power_in"))
      (node (ref "U3") (pin "2") (pinfunction "VIN_2") (pintype "power_in"))
    )
    (net (code "65") (name "VOL_CHECK") (class "Default")
      (node (ref "R4") (pin "1") (pinfunction "1_1") (pintype "passive"))
      (node (ref "R5") (pin "2") (pinfunction "2_2") (pintype "passive"))
      (node (ref "STM32F405RGT6") (pin "8") (pinfunction "PC0_8") (pintype "bidirectional"))
    )
    (net (code "66") (name "unconnected-(STM32F405RGT6-PA4{slash}USART2_CK-Pad20)") (class "Default")
      (node (ref "STM32F405RGT6") (pin "20") (pinfunction "PA4/USART2_CK_20") (pintype "bidirectional"))
    )
    (net (code "67") (name "unconnected-(STM32F405RGT6-PA6{slash}SPI1_MISO-Pad22)") (class "Default")
      (node (ref "STM32F405RGT6") (pin "22") (pinfunction "PA6/SPI1_MISO_22") (pintype "bidirectional"))
    )
    (net (code "68") (name "unconnected-(STM32F405RGT6-PA8-Pad41)") (class "Default")
      (node (ref "STM32F405RGT6") (pin "41") (pinfunction "PA8_41") (pintype "bidirectional"))
    )
    (net (code "69") (name "unconnected-(STM32F405RGT6-PA11-Pad44)") (class "Default")
      (node (ref "STM32F405RGT6") (pin "44") (pinfunction "PA11_44") (pintype "bidirectional"))
    )
    (net (code "70") (name "unconnected-(STM32F405RGT6-PA12-Pad45)") (class "Default")
      (node (ref "STM32F405RGT6") (pin "45") (pinfunction "PA12_45") (pintype "bidirectional"))
    )
    (net (code "71") (name "unconnected-(STM32F405RGT6-PB0-Pad26)") (class "Default")
      (node (ref "STM32F405RGT6") (pin "26") (pinfunction "PB0_26") (pintype "bidirectional"))
    )
    (net (code "72") (name "unconnected-(STM32F405RGT6-PB1-Pad27)") (class "Default")
      (node (ref "STM32F405RGT6") (pin "27") (pinfunction "PB1_27") (pintype "bidirectional"))
    )
    (net (code "73") (name "unconnected-(STM32F405RGT6-PB3-Pad55)") (class "Default")
      (node (ref "STM32F405RGT6") (pin "55") (pinfunction "PB3_55") (pintype "bidirectional"))
    )
    (net (code "74") (name "unconnected-(STM32F405RGT6-PB8-Pad61)") (class "Default")
      (node (ref "STM32F405RGT6") (pin "61") (pinfunction "PB8_61") (pintype "bidirectional"))
    )
    (net (code "75") (name "unconnected-(STM32F405RGT6-PB9-Pad62)") (class "Default")
      (node (ref "STM32F405RGT6") (pin "62") (pinfunction "PB9_62") (pintype "bidirectional"))
    )
    (net (code "76") (name "unconnected-(STM32F405RGT6-PB12-Pad33)") (class "Default")
      (node (ref "STM32F405RGT6") (pin "33") (pinfunction "PB12_33") (pintype "bidirectional"))
    )
    (net (code "77") (name "unconnected-(STM32F405RGT6-PB13-Pad34)") (class "Default")
      (node (ref "STM32F405RGT6") (pin "34") (pinfunction "PB13_34") (pintype "bidirectional"))
    )
    (net (code "78") (name "unconnected-(STM32F405RGT6-PB14-Pad35)") (class "Default")
      (node (ref "STM32F405RGT6") (pin "35") (pinfunction "PB14_35") (pintype "bidirectional"))
    )
    (net (code "79") (name "unconnected-(STM32F405RGT6-PC2{slash}SPI2_MISO-Pad10)") (class "Default")
      (node (ref "STM32F405RGT6") (pin "10") (pinfunction "PC2/SPI2_MISO_10") (pintype "bidirectional"))
    )
    (net (code "80") (name "unconnected-(STM32F405RGT6-PC4-Pad24)") (class "Default")
      (node (ref "STM32F405RGT6") (pin "24") (pinfunction "PC4_24") (pintype "bidirectional"))
    )
    (net (code "81") (name "unconnected-(STM32F405RGT6-PC5-Pad25)") (class "Default")
      (node (ref "STM32F405RGT6") (pin "25") (pinfunction "PC5_25") (pintype "bidirectional"))
    )
    (net (code "82") (name "unconnected-(STM32F405RGT6-PC15{slash}OSC32_OUT-Pad4)") (class "Default")
      (node (ref "STM32F405RGT6") (pin "4") (pinfunction "PC15/OSC32_OUT_4") (pintype "bidirectional"))
    )
    (net (code "83") (name "unconnected-(STM32F405RGT6-PH0{slash}OSC_IN-Pad5)") (class "Default")
      (node (ref "STM32F405RGT6") (pin "5") (pinfunction "PH0/OSC_IN_5") (pintype "bidirectional"))
    )
    (net (code "84") (name "unconnected-(U2-CM1-Pad11)") (class "Default")
      (node (ref "U2") (pin "11") (pinfunction "CM1_11") (pintype "output"))
    )
    (net (code "85") (name "unconnected-(U2-CM2-Pad7)") (class "Default")
      (node (ref "U2") (pin "7") (pinfunction "CM2_7") (pintype "output"))
    )
    (net (code "86") (name "unconnected-(U2-NFAULT-Pad12)") (class "Default")
      (node (ref "U2") (pin "12") (pinfunction "NFAULT_12") (pintype "output"))
    )
    (net (code "87") (name "unconnected-(U3-CM1-Pad11)") (class "Default")
      (node (ref "U3") (pin "11") (pinfunction "CM1_11") (pintype "output"))
    )
    (net (code "88") (name "unconnected-(U3-CM2-Pad7)") (class "Default")
      (node (ref "U3") (pin "7") (pinfunction "CM2_7") (pintype "output"))
    )
    (net (code "89") (name "unconnected-(U3-NFAULT-Pad12)") (class "Default")
      (node (ref "U3") (pin "12") (pinfunction "NFAULT_12") (pintype "output"))
    )
    (net (code "90") (name "unconnected-(U4-INT1-Pad4)") (class "Default")
      (node (ref "U4") (pin "4") (pinfunction "INT1_4") (pintype "output"))
    )
    (net (code "91") (name "unconnected-(U4-INT2-Pad9)") (class "Default")
      (node (ref "U4") (pin "9") (pinfunction "INT2_9") (pintype "output"))
    )
    (net (code "92") (name "unconnected-(U4-OCS_AUX-Pad10)") (class "Default")
      (node (ref "U4") (pin "10") (pinfunction "OCS_AUX_10") (pintype "bidirectional"))
    )
    (net (code "93") (name "unconnected-(U4-SDO_AUX-Pad11)") (class "Default")
      (node (ref "U4") (pin "11") (pinfunction "SDO_AUX_11") (pintype "bidirectional"))
    )
  )
)
